# PCB_BLU1.net
KiCad netlist of a schematic drawn in Altium Designer
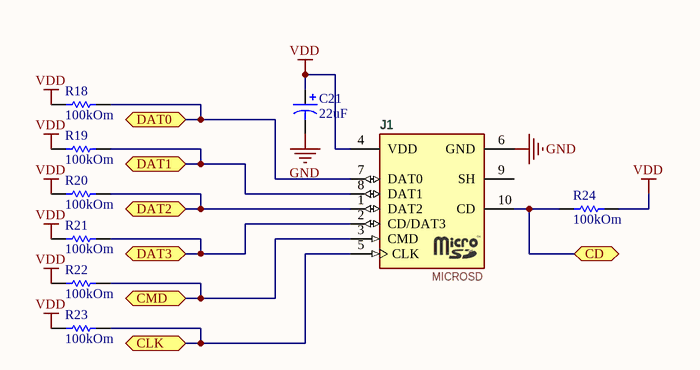
[diagram p0: PCB_BLU1.SchDoc]

(export (version "E")
  (design (tool "Eeschema 10.0.6"))
  (components
    (comp (ref "C21")
      (value "22uF")
      (footprint "6032")
      (fields (field (name "PUBLISHER") "Altium Limited"))
      (libsource (lib "Vishay Sprague Tantalum Chip Capacitor") (part "CWR11DH226M"))
    )
    (comp (ref "J1")
      (value "MICROSD")
      (footprint "MICROSD")
      (description "Memory Card Connectors Molex 504528-0892")
      (libsource (lib "MICROSD") (part "MICROSD"))
    )
    (comp (ref "R18")
      (value "100kOm")
      (footprint "RES0201R")
      (description "Resistor")
      (libsource (lib "PassiveSMT") (part "Resistor1"))
    )
    (comp (ref "R19")
      (value "100kOm")
      (footprint "RES0201R")
      (description "Resistor")
      (libsource (lib "PassiveSMT") (part "Resistor1"))
    )
    (comp (ref "R20")
      (value "100kOm")
      (footprint "RES0201R")
      (description "Resistor")
      (libsource (lib "PassiveSMT") (part "Resistor1"))
    )
    (comp (ref "R21")
      (value "100kOm")
      (footprint "RES0201R")
      (description "Resistor")
      (libsource (lib "PassiveSMT") (part "Resistor1"))
    )
    (comp (ref "R22")
      (value "100kOm")
      (footprint "RES0201R")
      (description "Resistor")
      (libsource (lib "PassiveSMT") (part "Resistor1"))
    )
    (comp (ref "R23")
      (value "100kOm")
      (footprint "RES0201R")
      (description "Resistor")
      (libsource (lib "PassiveSMT") (part "Resistor1"))
    )
    (comp (ref "R24")
      (value "100kOm")
      (footprint "RES0201R")
      (description "Resistor")
      (libsource (lib "PassiveSMT") (part "Resistor1"))
    )
  )
  (nets
    (net (code "1") (name "/CD") (class "Default")
      (node (ref "J1") (pin "10") (pinfunction "CD_10") (pintype "passive"))
      (node (ref "R24") (pin "2") (pinfunction "2_2") (pintype "passive"))
    )
    (net (code "2") (name "/CLK") (class "Default")
      (node (ref "J1") (pin "5") (pinfunction "CLK_5") (pintype "input"))
      (node (ref "R23") (pin "1") (pinfunction "1_1") (pintype "passive"))
    )
    (net (code "3") (name "/CMD") (class "Default")
      (node (ref "J1") (pin "3") (pinfunction "CMD_3") (pintype "input"))
      (node (ref "R22") (pin "1") (pinfunction "1_1") (pintype "passive"))
    )
    (net (code "4") (name "/DAT0") (class "Default")
      (node (ref "J1") (pin "7") (pinfunction "DAT0_7") (pintype "bidirectional"))
      (node (ref "R18") (pin "1") (pinfunction "1_1") (pintype "passive"))
    )
    (net (code "5") (name "/DAT1") (class "Default")
      (node (ref "J1") (pin "8") (pinfunction "DAT1_8") (pintype "bidirectional"))
      (node (ref "R19") (pin "1") (pinfunction "1_1") (pintype "passive"))
    )
    (net (code "6") (name "/DAT2") (class "Default")
      (node (ref "J1") (pin "1") (pinfunction "DAT2_1") (pintype "bidirectional"))
      (node (ref "R20") (pin "1") (pinfunction "1_1") (pintype "passive"))
    )
    (net (code "7") (name "/DAT3") (class "Default")
      (node (ref "J1") (pin "2") (pinfunction "CD/DAT3_2") (pintype "bidirectional"))
      (node (ref "R21") (pin "1") (pinfunction "1_1") (pintype "passive"))
    )
    (net (code "8") (name "GND") (class "Default")
      (node (ref "C21") (pin "2") (pinfunction "2_2") (pintype "passive"))
      (node (ref "J1") (pin "6") (pinfunction "GND_6") (pintype "power_in"))
    )
    (net (code "9") (name "VDD") (class "Default")
      (node (ref "C21") (pin "1") (pinfunction "1_1") (pintype "passive"))
      (node (ref "J1") (pin "4") (pinfunction "VDD_4") (pintype "power_in"))
      (node (ref "R18") (pin "2") (pinfunction "2_2") (pintype "passive"))
      (node (ref "R19") (pin "2") (pinfunction "2_2") (pintype "passive"))
      (node (ref "R20") (pin "2") (pinfunction "2_2") (pintype "passive"))
      (node (ref "R21") (pin "2") (pinfunction "2_2") (pintype "passive"))
      (node (ref "R22") (pin "2") (pinfunction "2_2") (pintype "passive"))
      (node (ref "R23") (pin "2") (pinfunction "2_2") (pintype "passive"))
      (node (ref "R24") (pin "1") (pinfunction "1_1") (pintype "passive"))
    )
    (net (code "10") (name "unconnected-(J1-SH-Pad9)") (class "Default")
      (node (ref "J1") (pin "9") (pinfunction "SH_9") (pintype "passive"))
    )
  )
)
